# PCB_DA2.net
KiCad netlist of a schematic drawn in Altium Designer
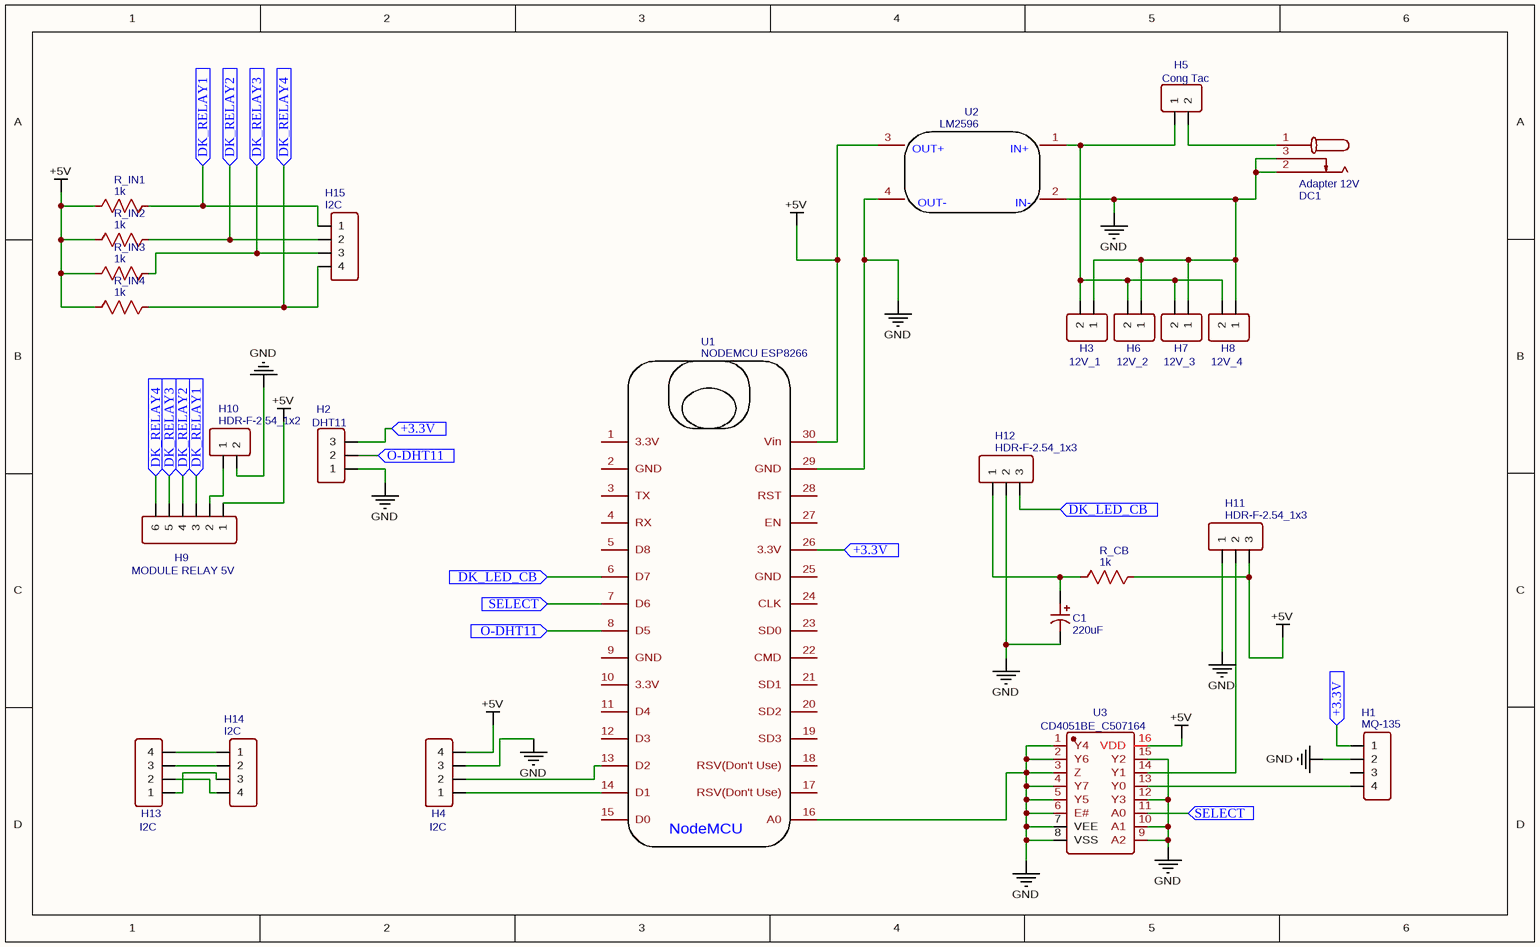
[diagram p0: PCB_DA2.schdoc]

(export (version "E")
  (design (tool "Eeschema 10.0.6"))
  (components
    (comp (ref "C1")
      (value "220uF")
      (footprint "CAP-TH_BD10.0-P5.00-D0.6-FD")
      (fields
        (field (name "MANUFACTURER") "ELNA(伊娜)")
        (field (name "MANUFACTURER PART") "RFO-35V221MH3P#")
        (field (name "CONTRIBUTOR") "lcsc")
      )
      (libsource (lib "altium-import") (part "root_3_220uF_"))
    )
    (comp (ref "DC1")
      (value "Adapter 12V")
      (footprint "DC-IN-TH_DC005")
      (fields (field (name "MANUFACTURER") "SOFNG") (field (name "MANUFACTURER PART") "DC005-2.0MM"))
      (libsource (lib "altium-import") (part "root_2_Adapter 12V_"))
    )
    (comp (ref "H1")
      (value "MQ-135")
      (footprint "HDR-F-2.54_1X4")
      (fields (field (name "CONTRIBUTOR") "LCEDA_Lib"))
      (libsource (lib "altium-import") (part "root_0_MQ-135_"))
    )
    (comp (ref "H2")
      (value "DHT11")
      (footprint "HDR-F-2.54_1X3")
      (fields (field (name "CONTRIBUTOR") "LCEDA_Lib"))
      (libsource (lib "altium-import") (part "root_2_DHT11_"))
    )
    (comp (ref "H3")
      (value "12V_1")
      (footprint "HDR-F-2.54_1X2")
      (fields (field (name "CONTRIBUTOR") "LCEDA_Lib"))
      (libsource (lib "altium-import") (part "root_3_12V_1_"))
    )
    (comp (ref "H4")
      (value "I2C")
      (footprint "HDR-F-2.54_1X4")
      (fields (field (name "CONTRIBUTOR") "LCEDA_Lib"))
      (libsource (lib "altium-import") (part "root_2_I2C_"))
    )
    (comp (ref "H5")
      (value "Cong Tac")
      (footprint "HDR-F-2.54_1X2")
      (fields (field (name "CONTRIBUTOR") "LCEDA_Lib"))
      (libsource (lib "altium-import") (part "root_1_Cong Tac_"))
    )
    (comp (ref "H6")
      (value "12V_2")
      (footprint "HDR-F-2.54_1X2")
      (fields (field (name "CONTRIBUTOR") "LCEDA_Lib"))
      (libsource (lib "altium-import") (part "root_3_12V_2_"))
    )
    (comp (ref "H7")
      (value "12V_3")
      (footprint "HDR-F-2.54_1X2")
      (fields (field (name "CONTRIBUTOR") "LCEDA_Lib"))
      (libsource (lib "altium-import") (part "root_3_12V_3_"))
    )
    (comp (ref "H8")
      (value "12V_4")
      (footprint "HDR-F-2.54_1X2")
      (fields (field (name "CONTRIBUTOR") "LCEDA_Lib"))
      (libsource (lib "altium-import") (part "root_3_12V_4_"))
    )
    (comp (ref "H9")
      (value "MODULE RELAY 5V")
      (footprint "HDR-F-2.54_1X6")
      (fields (field (name "CONTRIBUTOR") "LCEDA_Lib"))
      (libsource (lib "altium-import") (part "root_3_MODULE RELAY 5V_"))
    )
    (comp (ref "H10")
      (value "HDR-F-2.54_1x2")
      (footprint "HDR-F-2.54_1X2")
      (fields (field (name "CONTRIBUTOR") "LCEDA_Lib"))
      (libsource (lib "altium-import") (part "root_1_HDR-F-2.54_1x2_"))
    )
    (comp (ref "H11")
      (value "HDR-F-2.54_1x3")
      (footprint "HDR-F-2.54_1X3")
      (fields (field (name "CONTRIBUTOR") "LCEDA_Lib"))
      (libsource (lib "altium-import") (part "root_1_HDR-F-2.54_1x3_"))
    )
    (comp (ref "H12")
      (value "HDR-F-2.54_1x3")
      (footprint "HDR-F-2.54_1X3")
      (fields (field (name "CONTRIBUTOR") "LCEDA_Lib"))
      (libsource (lib "altium-import") (part "root_1_HDR-F-2.54_1x3_"))
    )
    (comp (ref "H13")
      (value "I2C")
      (footprint "HDR-F-2.54_1X4")
      (fields (field (name "CONTRIBUTOR") "LCEDA_Lib"))
      (libsource (lib "altium-import") (part "root_2_I2C_"))
    )
    (comp (ref "H14")
      (value "I2C")
      (footprint "HDR-F-2.54_1X4")
      (fields (field (name "CONTRIBUTOR") "LCEDA_Lib"))
      (libsource (lib "altium-import") (part "root_0_I2C_"))
    )
    (comp (ref "H15")
      (value "I2C")
      (footprint "HDR-F-2.54_1X4")
      (fields (field (name "CONTRIBUTOR") "LCEDA_Lib"))
      (libsource (lib "altium-import") (part "root_0_I2C_"))
    )
    (comp (ref "R_CB")
      (value "1k")
      (footprint "R_AXIAL-0.5")
      (fields (field (name "CONTRIBUTOR") "LCEDA_Lib"))
      (libsource (lib "altium-import") (part "root_0_1k_"))
    )
    (comp (ref "R_IN1")
      (value "1k")
      (footprint "R_AXIAL-0.5")
      (fields (field (name "CONTRIBUTOR") "LCEDA_Lib"))
      (libsource (lib "altium-import") (part "root_0_1k_"))
    )
    (comp (ref "R_IN2")
      (value "1k")
      (footprint "R_AXIAL-0.5")
      (fields (field (name "CONTRIBUTOR") "LCEDA_Lib"))
      (libsource (lib "altium-import") (part "root_0_1k_"))
    )
    (comp (ref "R_IN3")
      (value "1k")
      (footprint "R_AXIAL-0.5")
      (fields (field (name "CONTRIBUTOR") "LCEDA_Lib"))
      (libsource (lib "altium-import") (part "root_0_1k_"))
    )
    (comp (ref "R_IN4")
      (value "1k")
      (footprint "R_AXIAL-0.5")
      (fields (field (name "CONTRIBUTOR") "LCEDA_Lib"))
      (libsource (lib "altium-import") (part "root_0_1k_"))
    )
    (comp (ref "U1")
      (value "NODEMCU ESP8266")
      (footprint "ESP12E_DEVKIT-V1")
      (fields (field (name "CONTRIBUTOR") "Milinda Bandara"))
      (libsource (lib "altium-import") (part "root_0_NODEMCU ESP8266_"))
    )
    (comp (ref "U2")
      (value "LM2596")
      (footprint "LM2596DC_DC")
      (fields (field (name "CONTRIBUTOR") "utk.pekerjaan"))
      (libsource (lib "altium-import") (part "root_0_LM2596_"))
    )
    (comp (ref "U3")
      (value "CD4051BE_C507164")
      (footprint "DIP-16_L20.0-W6.4-P2.54-LS7.6-BL")
      (fields
        (field (name "MANUFACTURER") "HGSEMI(华冠)")
        (field (name "MANUFACTURER PART") "CD4051BE")
        (field (name "CONTRIBUTOR") "LCSC")
      )
      (libsource (lib "altium-import") (part "root_0_CD4051BE_C507164_"))
    )
  )
  (nets
    (net (code "1") (name "+5V") (class "Default")
      (node (ref "H11") (pin "3") (pinfunction "3_3") (pintype "passive"))
      (node (ref "H4") (pin "4") (pinfunction "4_4") (pintype "passive"))
      (node (ref "H9") (pin "1") (pinfunction "1_1") (pintype "passive"))
      (node (ref "R_CB") (pin "2") (pinfunction "2_2") (pintype "passive"))
      (node (ref "R_IN1") (pin "1") (pinfunction "1_1") (pintype "passive"))
      (node (ref "R_IN2") (pin "1") (pinfunction "1_1") (pintype "passive"))
      (node (ref "R_IN3") (pin "1") (pinfunction "1_1") (pintype "passive"))
      (node (ref "R_IN4") (pin "1") (pinfunction "1_1") (pintype "passive"))
      (node (ref "U1") (pin "30") (pinfunction "Vin_30") (pintype "passive"))
      (node (ref "U2") (pin "3") (pinfunction "3_3") (pintype "passive"))
      (node (ref "U3") (pin "16") (pinfunction "VDD_16") (pintype "passive"))
    )
    (net (code "2") (name "/+3.3V") (class "Default")
      (node (ref "H1") (pin "1") (pinfunction "1_1") (pintype "passive"))
      (node (ref "H2") (pin "3") (pinfunction "3_3") (pintype "passive"))
      (node (ref "U1") (pin "26") (pinfunction "3.3V_26") (pintype "passive"))
    )
    (net (code "3") (name "/DK_LED_CB") (class "Default")
      (node (ref "H12") (pin "3") (pinfunction "3_3") (pintype "passive"))
      (node (ref "U1") (pin "6") (pinfunction "D7_6") (pintype "passive"))
    )
    (net (code "4") (name "/DK_RELAY1") (class "Default")
      (node (ref "H15") (pin "1") (pinfunction "1_1") (pintype "passive"))
      (node (ref "H9") (pin "3") (pinfunction "3_3") (pintype "passive"))
      (node (ref "R_IN1") (pin "2") (pinfunction "2_2") (pintype "passive"))
    )
    (net (code "5") (name "/DK_RELAY2") (class "Default")
      (node (ref "H15") (pin "2") (pinfunction "2_2") (pintype "passive"))
      (node (ref "H9") (pin "4") (pinfunction "4_4") (pintype "passive"))
      (node (ref "R_IN2") (pin "2") (pinfunction "2_2") (pintype "passive"))
    )
    (net (code "6") (name "/DK_RELAY3") (class "Default")
      (node (ref "H15") (pin "3") (pinfunction "3_3") (pintype "passive"))
      (node (ref "H9") (pin "5") (pinfunction "5_5") (pintype "passive"))
      (node (ref "R_IN3") (pin "2") (pinfunction "2_2") (pintype "passive"))
    )
    (net (code "7") (name "/DK_RELAY4") (class "Default")
      (node (ref "H15") (pin "4") (pinfunction "4_4") (pintype "passive"))
      (node (ref "H9") (pin "6") (pinfunction "6_6") (pintype "passive"))
      (node (ref "R_IN4") (pin "2") (pinfunction "2_2") (pintype "passive"))
    )
    (net (code "8") (name "/O-DHT11") (class "Default")
      (node (ref "H2") (pin "2") (pinfunction "2_2") (pintype "passive"))
      (node (ref "U1") (pin "8") (pinfunction "D5_8") (pintype "passive"))
    )
    (net (code "9") (name "/SELECT") (class "Default")
      (node (ref "U1") (pin "7") (pinfunction "D6_7") (pintype "passive"))
      (node (ref "U3") (pin "11") (pinfunction "A0_11") (pintype "passive"))
    )
    (net (code "10") (name "GND") (class "Default")
      (node (ref "C1") (pin "2") (pinfunction "2_2") (pintype "passive"))
      (node (ref "DC1") (pin "2") (pinfunction "2_2") (pintype "passive"))
      (node (ref "DC1") (pin "3") (pinfunction "3_3") (pintype "passive"))
      (node (ref "H1") (pin "2") (pinfunction "2_2") (pintype "passive"))
      (node (ref "H10") (pin "2") (pinfunction "2_2") (pintype "passive"))
      (node (ref "H11") (pin "1") (pinfunction "1_1") (pintype "passive"))
      (node (ref "H12") (pin "2") (pinfunction "2_2") (pintype "passive"))
      (node (ref "H2") (pin "1") (pinfunction "1_1") (pintype "passive"))
      (node (ref "H3") (pin "1") (pinfunction "1_1") (pintype "passive"))
      (node (ref "H4") (pin "3") (pinfunction "3_3") (pintype "passive"))
      (node (ref "H6") (pin "1") (pinfunction "1_1") (pintype "passive"))
      (node (ref "H7") (pin "1") (pinfunction "1_1") (pintype "passive"))
      (node (ref "H8") (pin "1") (pinfunction "1_1") (pintype "passive"))
      (node (ref "U1") (pin "16") (pinfunction "A0_16") (pintype "passive"))
      (node (ref "U1") (pin "29") (pinfunction "GND_29") (pintype "passive"))
      (node (ref "U2") (pin "2") (pinfunction "2_2") (pintype "passive"))
      (node (ref "U2") (pin "4") (pinfunction "4_4") (pintype "passive"))
      (node (ref "U3") (pin "1") (pinfunction "Y4_1") (pintype "passive"))
      (node (ref "U3") (pin "10") (pinfunction "A1_10") (pintype "passive"))
      (node (ref "U3") (pin "12") (pinfunction "Y3_12") (pintype "passive"))
      (node (ref "U3") (pin "15") (pinfunction "Y2_15") (pintype "passive"))
      (node (ref "U3") (pin "2") (pinfunction "Y6_2") (pintype "passive"))
      (node (ref "U3") (pin "3") (pinfunction "Z_3") (pintype "passive"))
      (node (ref "U3") (pin "4") (pinfunction "Y7_4") (pintype "passive"))
      (node (ref "U3") (pin "5") (pinfunction "Y5_5") (pintype "passive"))
      (node (ref "U3") (pin "6") (pinfunction "E#_6") (pintype "passive"))
      (node (ref "U3") (pin "7") (pinfunction "VEE_7") (pintype "passive"))
      (node (ref "U3") (pin "8") (pinfunction "VSS_8") (pintype "passive"))
      (node (ref "U3") (pin "9") (pinfunction "A2_9") (pintype "passive"))
    )
    (net (code "11") (name "Net-(C1-Pad1)") (class "Default")
      (node (ref "C1") (pin "1") (pinfunction "1_1") (pintype "passive"))
      (node (ref "H12") (pin "1") (pinfunction "1_1") (pintype "passive"))
      (node (ref "R_CB") (pin "1") (pinfunction "1_1") (pintype "passive"))
    )
    (net (code "12") (name "Net-(DC1-Pad1)") (class "Default")
      (node (ref "DC1") (pin "1") (pinfunction "1_1") (pintype "passive"))
      (node (ref "H5") (pin "2") (pinfunction "2_2") (pintype "passive"))
    )
    (net (code "13") (name "Net-(H3-Pad2)") (class "Default")
      (node (ref "H3") (pin "2") (pinfunction "2_2") (pintype "passive"))
      (node (ref "H5") (pin "1") (pinfunction "1_1") (pintype "passive"))
      (node (ref "H6") (pin "2") (pinfunction "2_2") (pintype "passive"))
      (node (ref "H7") (pin "2") (pinfunction "2_2") (pintype "passive"))
      (node (ref "H8") (pin "2") (pinfunction "2_2") (pintype "passive"))
      (node (ref "U2") (pin "1") (pinfunction "1_1") (pintype "passive"))
    )
    (net (code "14") (name "Net-(H10-Pad1)") (class "Default")
      (node (ref "H10") (pin "1") (pinfunction "1_1") (pintype "passive"))
      (node (ref "H9") (pin "2") (pinfunction "2_2") (pintype "passive"))
    )
    (net (code "15") (name "Net-(H13-Pad1)") (class "Default")
      (node (ref "H13") (pin "1") (pinfunction "1_1") (pintype "passive"))
      (node (ref "H14") (pin "3") (pinfunction "3_3") (pintype "passive"))
    )
    (net (code "16") (name "Net-(H13-Pad2)") (class "Default")
      (node (ref "H13") (pin "2") (pinfunction "2_2") (pintype "passive"))
      (node (ref "H14") (pin "4") (pinfunction "4_4") (pintype "passive"))
    )
    (net (code "17") (name "Net-(H13-Pad3)") (class "Default")
      (node (ref "H13") (pin "3") (pinfunction "3_3") (pintype "passive"))
      (node (ref "H14") (pin "2") (pinfunction "2_2") (pintype "passive"))
    )
    (net (code "18") (name "Net-(H13-Pad4)") (class "Default")
      (node (ref "H13") (pin "4") (pinfunction "4_4") (pintype "passive"))
      (node (ref "H14") (pin "1") (pinfunction "1_1") (pintype "passive"))
    )
    (net (code "19") (name "Net-(U1-D1)") (class "Default")
      (node (ref "H4") (pin "1") (pinfunction "1_1") (pintype "passive"))
      (node (ref "U1") (pin "14") (pinfunction "D1_14") (pintype "passive"))
    )
    (net (code "20") (name "Net-(U1-D2)") (class "Default")
      (node (ref "H4") (pin "2") (pinfunction "2_2") (pintype "passive"))
      (node (ref "U1") (pin "13") (pinfunction "D2_13") (pintype "passive"))
    )
    (net (code "21") (name "Net-(U3-Y0)") (class "Default")
      (node (ref "H1") (pin "4") (pinfunction "4_4") (pintype "passive"))
      (node (ref "U3") (pin "13") (pinfunction "Y0_13") (pintype "passive"))
    )
    (net (code "22") (name "Net-(U3-Y1)") (class "Default")
      (node (ref "H11") (pin "2") (pinfunction "2_2") (pintype "passive"))
      (node (ref "U3") (pin "14") (pinfunction "Y1_14") (pintype "passive"))
    )
    (net (code "23") (name "unconnected-(H1-Pad3)") (class "Default")
      (node (ref "H1") (pin "3") (pinfunction "3_3") (pintype "passive"))
    )
    (net (code "24") (name "unconnected-(U1-3.3V-Pad1)") (class "Default")
      (node (ref "U1") (pin "1") (pinfunction "3.3V_1") (pintype "passive"))
    )
    (net (code "25") (name "unconnected-(U1-3.3V-Pad10)") (class "Default")
      (node (ref "U1") (pin "10") (pinfunction "3.3V_10") (pintype "passive"))
    )
    (net (code "26") (name "unconnected-(U1-CLK-Pad24)") (class "Default")
      (node (ref "U1") (pin "24") (pinfunction "CLK_24") (pintype "passive"))
    )
    (net (code "27") (name "unconnected-(U1-CMD-Pad22)") (class "Default")
      (node (ref "U1") (pin "22") (pinfunction "CMD_22") (pintype "passive"))
    )
    (net (code "28") (name "unconnected-(U1-D0-Pad15)") (class "Default")
      (node (ref "U1") (pin "15") (pinfunction "D0_15") (pintype "passive"))
    )
    (net (code "29") (name "unconnected-(U1-D3-Pad12)") (class "Default")
      (node (ref "U1") (pin "12") (pinfunction "D3_12") (pintype "passive"))
    )
    (net (code "30") (name "unconnected-(U1-D4-Pad11)") (class "Default")
      (node (ref "U1") (pin "11") (pinfunction "D4_11") (pintype "passive"))
    )
    (net (code "31") (name "unconnected-(U1-D8-Pad5)") (class "Default")
      (node (ref "U1") (pin "5") (pinfunction "D8_5") (pintype "passive"))
    )
    (net (code "32") (name "unconnected-(U1-EN-Pad27)") (class "Default")
      (node (ref "U1") (pin "27") (pinfunction "EN_27") (pintype "passive"))
    )
    (net (code "33") (name "unconnected-(U1-GND-Pad2)") (class "Default")
      (node (ref "U1") (pin "2") (pinfunction "GND_2") (pintype "passive"))
    )
    (net (code "34") (name "unconnected-(U1-GND-Pad9)") (class "Default")
      (node (ref "U1") (pin "9") (pinfunction "GND_9") (pintype "passive"))
    )
    (net (code "35") (name "unconnected-(U1-GND-Pad25)") (class "Default")
      (node (ref "U1") (pin "25") (pinfunction "GND_25") (pintype "passive"))
    )
    (net (code "36") (name "unconnected-(U1-RST-Pad28)") (class "Default")
      (node (ref "U1") (pin "28") (pinfunction "RST_28") (pintype "passive"))
    )
    (net (code "37") (name "unconnected-(U1-RSV(Don't_Use)-Pad17)") (class "Default")
      (node (ref "U1") (pin "17") (pinfunction "RSV(Don't_Use)_17") (pintype "passive"))
    )
    (net (code "38") (name "unconnected-(U1-RSV(Don't_Use)-Pad18)") (class "Default")
      (node (ref "U1") (pin "18") (pinfunction "RSV(Don't_Use)_18") (pintype "passive"))
    )
    (net (code "39") (name "unconnected-(U1-RX-Pad4)") (class "Default")
      (node (ref "U1") (pin "4") (pinfunction "RX_4") (pintype "passive"))
    )
    (net (code "40") (name "unconnected-(U1-SD0-Pad23)") (class "Default")
      (node (ref "U1") (pin "23") (pinfunction "SD0_23") (pintype "passive"))
    )
    (net (code "41") (name "unconnected-(U1-SD1-Pad21)") (class "Default")
      (node (ref "U1") (pin "21") (pinfunction "SD1_21") (pintype "passive"))
    )
    (net (code "42") (name "unconnected-(U1-SD2-Pad20)") (class "Default")
      (node (ref "U1") (pin "20") (pinfunction "SD2_20") (pintype "passive"))
    )
    (net (code "43") (name "unconnected-(U1-SD3-Pad19)") (class "Default")
      (node (ref "U1") (pin "19") (pinfunction "SD3_19") (pintype "passive"))
    )
    (net (code "44") (name "unconnected-(U1-TX-Pad3)") (class "Default")
      (node (ref "U1") (pin "3") (pinfunction "TX_3") (pintype "passive"))
    )
  )
)
